# USBHeaders.net
KiCad netlist of a schematic drawn in Altium Designer
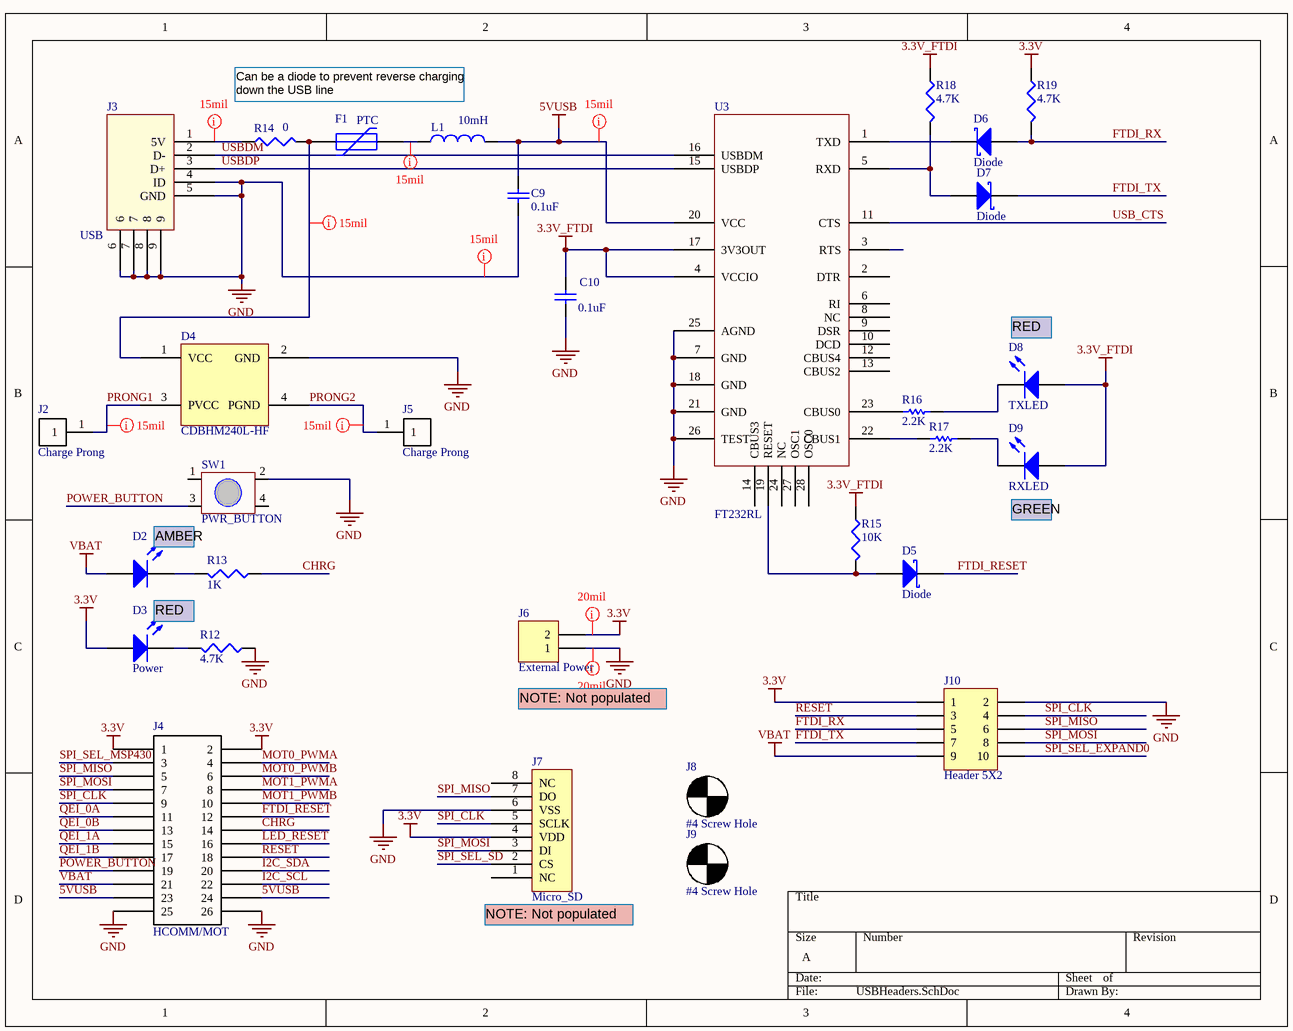
[diagram p0: USBHeaders.SchDoc]

(export (version "E")
  (design (tool "Eeschema 10.0.6"))
  (components
    (comp (ref "C9")
      (value "0.1uF")
      (footprint "CAPC1005L")
      (description "Capacitor")
      (fields (field (name "PUBLISHER") "Altium Limited"))
      (libsource (lib "Miscellaneous Devices") (part "Cap"))
    )
    (comp (ref "C10")
      (value "0.1uF")
      (footprint "CAPC1005L")
      (description "Capacitor")
      (fields (field (name "PUBLISHER") "Altium Limited"))
      (libsource (lib "Miscellaneous Devices") (part "Cap"))
    )
    (comp (ref "D2")
      (value "Charge")
      (footprint "SurfaceMount(603)")
      (description "Typical RED, GREEN, YELLOW, AMBER GaAs LED")
      (fields (field (name "PUBLISHER") "Altium Limited"))
      (libsource (lib "") (part "LED2_1"))
    )
    (comp (ref "D3") (value "Power") (footprint "SurfaceMount(603)") (libsource (lib "mrone") (part "LED")))
    (comp (ref "D4")
      (value "CDBHM240L-HF")
      (footprint "DIODEARRAY_2AMPS")
      (fields (field (name "MPN") "CDBHM240L-HF"))
      (libsource (lib "mrone") (part "DiodeArray2Amps"))
    )
    (comp (ref "D5")
      (value "Diode")
      (footprint "SurfaceMount(603)")
      (libsource (lib "mrone") (part "SchottkeyDiode"))
    )
    (comp (ref "D6")
      (value "Diode")
      (footprint "SurfaceMount(603)")
      (libsource (lib "mrone") (part "SchottkeyDiode"))
    )
    (comp (ref "D7")
      (value "Diode")
      (footprint "SurfaceMount(603)")
      (libsource (lib "mrone") (part "SchottkeyDiode"))
    )
    (comp (ref "D8")
      (value "TXLED")
      (footprint "SurfaceMount(603)")
      (description "Typical RED, GREEN, YELLOW, AMBER GaAs LED")
      (fields (field (name "PUBLISHER") "Altium Limited"))
      (libsource (lib "Miscellaneous Devices") (part "LED2"))
    )
    (comp (ref "D9")
      (value "RXLED")
      (footprint "SurfaceMount(603)")
      (description "Typical RED, GREEN, YELLOW, AMBER GaAs LED")
      (fields (field (name "PUBLISHER") "Altium Limited"))
      (libsource (lib "Miscellaneous Devices") (part "LED2"))
    )
    (comp (ref "F1")
      (value "PTC")
      (footprint "ERJ8G-1206")
      (description "Fuse")
      (fields (field (name "PUBLISHER") "Altium Limited"))
      (libsource (lib "mrone") (part "PTC_FUSE"))
    )
    (comp (ref "J2")
      (value "Charge Prong")
      (footprint "CHARGING_PRONG")
      (description "Charging Prong Hole with Plating")
      (libsource (lib "mrone") (part "CHARGE_PRONG"))
    )
    (comp (ref "J3")
      (value "USB")
      (footprint "USB Minib (thru-hole)")
      (libsource (lib "mrone") (part "USB-ConnTH"))
    )
    (comp (ref "J4")
      (value "HCOMM/MOT")
      (footprint "HeaderSM 13x2")
      (description "Header, 2X20, 50mil, IDC")
      (libsource (lib "mrone") (part "HCOMM/HMOT"))
    )
    (comp (ref "J5")
      (value "Charge Prong")
      (footprint "CHARGING_PRONG")
      (description "Charging Prong Hole with Plating")
      (libsource (lib "mrone") (part "CHARGE_PRONG"))
    )
    (comp (ref "J6")
      (value "External Power")
      (footprint "HDR1X2")
      (description "Header, 2-Pin")
      (fields (field (name "PUBLISHER") "Altium Limited"))
      (libsource (lib "Miscellaneous Connectors") (part "Header 2"))
    )
    (comp (ref "J7") (value "Micro_SD") (footprint "MICRO_SD") (libsource (lib "mrone") (part "MICRO_SD")))
    (comp (ref "J8")
      (value "#4 Screw Hole")
      (footprint "#4_Screw_Hole")
      (description "A mechanical hole for mounting the board")
      (libsource (lib "mrone") (part "Mechanical_Hole"))
    )
    (comp (ref "J9")
      (value "#4 Screw Hole")
      (footprint "#4_Screw_Hole")
      (description "A mechanical hole for mounting the board")
      (libsource (lib "mrone") (part "Mechanical_Hole"))
    )
    (comp (ref "J10")
      (value "Header 5X2")
      (footprint "HDR2X5")
      (description "Header, 5-Pin, Dual row")
      (fields (field (name "PUBLISHER") "Altium Limited"))
      (libsource (lib "mrone") (part "Header 5X2"))
    )
    (comp (ref "L1")
      (value "10mH")
      (footprint "INDC2012L")
      (description "Inductor")
      (fields (field (name "PUBLISHER") "Altium Limited"))
      (libsource (lib "Miscellaneous Devices") (part "Inductor"))
    )
    (comp (ref "R12")
      (value "4.7K")
      (footprint "RESC1608L")
      (description "Resistor")
      (fields (field (name "Comment") "Res3") (field (name "PUBLISHER") "Altium Limited"))
      (libsource (lib "Miscellaneous Devices") (part "Res3"))
    )
    (comp (ref "R13")
      (value "1K")
      (footprint "RESC1608L")
      (description "Resistor")
      (fields (field (name "Comment") "Res3") (field (name "PUBLISHER") "Altium Limited"))
      (libsource (lib "Miscellaneous Devices") (part "Res3"))
    )
    (comp (ref "R14")
      (value "0")
      (footprint "RESC1608L")
      (description "Resistor")
      (fields (field (name "Comment") "Res3") (field (name "PUBLISHER") "Altium Limited"))
      (libsource (lib "Miscellaneous Devices") (part "Res3"))
    )
    (comp (ref "R15")
      (value "10K")
      (footprint "RESC1608L")
      (description "Resistor")
      (fields (field (name "Comment") "Res3") (field (name "PUBLISHER") "Altium Limited"))
      (libsource (lib "Miscellaneous Devices") (part "Res3"))
    )
    (comp (ref "R16")
      (value "2.2K")
      (footprint "RESC1608L")
      (description "Resistor")
      (fields (field (name "PUBLISHER") "Altium Limited"))
      (libsource (lib "Miscellaneous Devices") (part "Res1"))
    )
    (comp (ref "R17")
      (value "2.2K")
      (footprint "RESC1608L")
      (description "Resistor")
      (fields (field (name "PUBLISHER") "Altium Limited"))
      (libsource (lib "Miscellaneous Devices") (part "Res1"))
    )
    (comp (ref "R18")
      (value "4.7K")
      (footprint "RESC1608L")
      (description "Resistor")
      (fields (field (name "Comment") "Res3") (field (name "PUBLISHER") "Altium Limited"))
      (libsource (lib "Miscellaneous Devices") (part "Res3"))
    )
    (comp (ref "R19")
      (value "4.7K")
      (footprint "RESC1608L")
      (description "Resistor")
      (fields (field (name "Comment") "Res3") (field (name "PUBLISHER") "Altium Limited"))
      (libsource (lib "Miscellaneous Devices") (part "Res3"))
    )
    (comp (ref "SW1")
      (value "PWR_BUTTON")
      (footprint "SwitchTall-TL330")
      (libsource (lib "mrone") (part "Switch-TL330"))
    )
    (comp (ref "U3") (value "FT232RL") (footprint "SSOP-28") (libsource (lib "mrone") (part "FT232RL")))
  )
  (nets
    (net (code "2") (name "/CHRG") (class "Default")
      (node (ref "J4") (pin "14") (pinfunction "14_14") (pintype "passive"))
      (node (ref "R13") (pin "1") (pinfunction "1_1") (pintype "passive"))
    )
    (net (code "3") (name "/FTDI_RESET") (class "Default")
      (node (ref "D5") (pin "1") (pinfunction "K_1") (pintype "passive"))
      (node (ref "J4") (pin "12") (pinfunction "12_12") (pintype "passive"))
    )
    (net (code "4") (name "/FTDI_RX") (class "Default")
      (node (ref "D6") (pin "2") (pinfunction "A_2") (pintype "passive"))
      (node (ref "J10") (pin "5") (pinfunction "5_5") (pintype "passive"))
      (node (ref "R19") (pin "2") (pinfunction "2_2") (pintype "passive"))
    )
    (net (code "5") (name "/FTDI_TX") (class "Default")
      (node (ref "D7") (pin "1") (pinfunction "K_1") (pintype "passive"))
      (node (ref "J10") (pin "7") (pinfunction "7_7") (pintype "passive"))
    )
    (net (code "6") (name "/I2C_SCL") (class "Default")
      (node (ref "J4") (pin "22") (pinfunction "22_22") (pintype "passive"))
    )
    (net (code "7") (name "/I2C_SDA") (class "Default")
      (node (ref "J4") (pin "20") (pinfunction "20_20") (pintype "passive"))
    )
    (net (code "8") (name "/LED_RESET") (class "Default")
      (node (ref "J4") (pin "16") (pinfunction "16_16") (pintype "passive"))
    )
    (net (code "9") (name "/MOT0_PWMA") (class "Default")
      (node (ref "J4") (pin "4") (pinfunction "4_4") (pintype "passive"))
    )
    (net (code "10") (name "/MOT0_PWMB") (class "Default")
      (node (ref "J4") (pin "6") (pinfunction "6_6") (pintype "passive"))
    )
    (net (code "11") (name "/MOT1_PWMA") (class "Default")
      (node (ref "J4") (pin "8") (pinfunction "8_8") (pintype "passive"))
    )
    (net (code "12") (name "/MOT1_PWMB") (class "Default")
      (node (ref "J4") (pin "10") (pinfunction "10_10") (pintype "passive"))
    )
    (net (code "13") (name "/POWER_BUTTON") (class "Default")
      (node (ref "J4") (pin "19") (pinfunction "19_19") (pintype "passive"))
      (node (ref "SW1") (pin "3") (pinfunction "3_3") (pintype "passive"))
    )
    (net (code "14") (name "/PRONG1") (class "Default")
      (node (ref "D4") (pin "3") (pinfunction "PVCC_3") (pintype "passive"))
      (node (ref "J2") (pin "1") (pinfunction "1_1") (pintype "passive"))
    )
    (net (code "15") (name "/PRONG2") (class "Default")
      (node (ref "D4") (pin "4") (pinfunction "PGND_4") (pintype "passive"))
      (node (ref "J5") (pin "1") (pinfunction "1_1") (pintype "passive"))
    )
    (net (code "16") (name "/QEI_0A") (class "Default")
      (node (ref "J4") (pin "11") (pinfunction "11_11") (pintype "passive"))
    )
    (net (code "17") (name "/QEI_0B") (class "Default")
      (node (ref "J4") (pin "13") (pinfunction "13_13") (pintype "passive"))
    )
    (net (code "18") (name "/QEI_1A") (class "Default")
      (node (ref "J4") (pin "15") (pinfunction "15_15") (pintype "passive"))
    )
    (net (code "19") (name "/QEI_1B") (class "Default")
      (node (ref "J4") (pin "17") (pinfunction "17_17") (pintype "passive"))
    )
    (net (code "20") (name "/RESET") (class "Default")
      (node (ref "J10") (pin "3") (pinfunction "3_3") (pintype "passive"))
      (node (ref "J4") (pin "18") (pinfunction "18_18") (pintype "passive"))
    )
    (net (code "21") (name "/SPI_CLK") (class "Default")
      (node (ref "J10") (pin "4") (pinfunction "4_4") (pintype "passive"))
      (node (ref "J4") (pin "9") (pinfunction "9_9") (pintype "passive"))
      (node (ref "J7") (pin "5") (pinfunction "SCLK_5") (pintype "passive"))
    )
    (net (code "22") (name "/SPI_MISO") (class "Default")
      (node (ref "J10") (pin "6") (pinfunction "6_6") (pintype "passive"))
      (node (ref "J4") (pin "5") (pinfunction "5_5") (pintype "passive"))
      (node (ref "J7") (pin "7") (pinfunction "DO_7") (pintype "passive"))
    )
    (net (code "23") (name "/SPI_MOSI") (class "Default")
      (node (ref "J10") (pin "8") (pinfunction "8_8") (pintype "passive"))
      (node (ref "J4") (pin "7") (pinfunction "7_7") (pintype "passive"))
      (node (ref "J7") (pin "3") (pinfunction "DI_3") (pintype "passive"))
    )
    (net (code "24") (name "/SPI_SEL_EXPAND0") (class "Default")
      (node (ref "J10") (pin "10") (pinfunction "10_10") (pintype "passive"))
    )
    (net (code "25") (name "/SPI_SEL_MSP430") (class "Default")
      (node (ref "J4") (pin "3") (pinfunction "3_3") (pintype "passive"))
    )
    (net (code "26") (name "/SPI_SEL_SD") (class "Default")
      (node (ref "J7") (pin "2") (pinfunction "CS_2") (pintype "passive"))
    )
    (net (code "27") (name "/USBDM") (class "Default")
      (node (ref "J3") (pin "2") (pinfunction "D-_2") (pintype "passive"))
      (node (ref "U3") (pin "16") (pinfunction "USBDM_16") (pintype "passive"))
    )
    (net (code "28") (name "/USBDP") (class "Default")
      (node (ref "J3") (pin "3") (pinfunction "D+_3") (pintype "passive"))
      (node (ref "U3") (pin "15") (pinfunction "USBDP_15") (pintype "passive"))
    )
    (net (code "29") (name "/USB_CTS") (class "Default")
      (node (ref "U3") (pin "11") (pinfunction "CTS_11") (pintype "passive"))
    )
    (net (code "30") (name "3.3V") (class "Default")
      (node (ref "D3") (pin "1") (pinfunction "A_1") (pintype "passive"))
      (node (ref "J10") (pin "1") (pinfunction "1_1") (pintype "passive"))
      (node (ref "J4") (pin "1") (pinfunction "1_1") (pintype "passive"))
      (node (ref "J4") (pin "2") (pinfunction "2_2") (pintype "passive"))
      (node (ref "J6") (pin "2") (pinfunction "2_2") (pintype "passive"))
      (node (ref "J7") (pin "4") (pinfunction "VDD_4") (pintype "passive"))
      (node (ref "R19") (pin "1") (pinfunction "1_1") (pintype "passive"))
    )
    (net (code "31") (name "3.3V_FTDI") (class "Default")
      (node (ref "C10") (pin "2") (pinfunction "2_2") (pintype "passive"))
      (node (ref "D8") (pin "1") (pinfunction "A_1") (pintype "passive"))
      (node (ref "D9") (pin "1") (pinfunction "A_1") (pintype "passive"))
      (node (ref "R15") (pin "1") (pinfunction "1_1") (pintype "passive"))
      (node (ref "R18") (pin "1") (pinfunction "1_1") (pintype "passive"))
      (node (ref "U3") (pin "17") (pinfunction "3V3OUT_17") (pintype "passive"))
      (node (ref "U3") (pin "4") (pinfunction "VCCIO_4") (pintype "passive"))
    )
    (net (code "32") (name "5VUSB") (class "Default")
      (node (ref "C9") (pin "2") (pinfunction "2_2") (pintype "passive"))
      (node (ref "J4") (pin "23") (pinfunction "23_23") (pintype "passive"))
      (node (ref "J4") (pin "24") (pinfunction "24_24") (pintype "passive"))
      (node (ref "L1") (pin "2") (pinfunction "2_2") (pintype "passive"))
      (node (ref "U3") (pin "20") (pinfunction "VCC_20") (pintype "passive"))
    )
    (net (code "33") (name "GND") (class "Default")
      (node (ref "C10") (pin "1") (pinfunction "1_1") (pintype "passive"))
      (node (ref "C9") (pin "1") (pinfunction "1_1") (pintype "passive"))
      (node (ref "D4") (pin "2") (pinfunction "GND_2") (pintype "passive"))
      (node (ref "J10") (pin "2") (pinfunction "2_2") (pintype "passive"))
      (node (ref "J3") (pin "4") (pinfunction "ID_4") (pintype "passive"))
      (node (ref "J3") (pin "5") (pinfunction "GND_5") (pintype "passive"))
      (node (ref "J3") (pin "6") (pinfunction "6_6") (pintype "passive"))
      (node (ref "J3") (pin "7") (pinfunction "7_7") (pintype "passive"))
      (node (ref "J3") (pin "8") (pinfunction "8_8") (pintype "passive"))
      (node (ref "J3") (pin "9") (pinfunction "9_9") (pintype "passive"))
      (node (ref "J4") (pin "25") (pinfunction "25_25") (pintype "passive"))
      (node (ref "J4") (pin "26") (pinfunction "26_26") (pintype "passive"))
      (node (ref "J6") (pin "1") (pinfunction "1_1") (pintype "passive"))
      (node (ref "J7") (pin "6") (pinfunction "VSS_6") (pintype "passive"))
      (node (ref "R12") (pin "1") (pinfunction "1_1") (pintype "passive"))
      (node (ref "SW1") (pin "2") (pinfunction "2_2") (pintype "passive"))
      (node (ref "U3") (pin "18") (pinfunction "GND_18") (pintype "passive"))
      (node (ref "U3") (pin "21") (pinfunction "GND_21") (pintype "passive"))
      (node (ref "U3") (pin "25") (pinfunction "AGND_25") (pintype "passive"))
      (node (ref "U3") (pin "26") (pinfunction "TEST_26") (pintype "passive"))
      (node (ref "U3") (pin "7") (pinfunction "GND_7") (pintype "passive"))
    )
    (net (code "34") (name "Net-(D2-K)") (class "Default")
      (node (ref "D2") (pin "2") (pinfunction "K_2") (pintype "passive"))
      (node (ref "R13") (pin "2") (pinfunction "2_2") (pintype "passive"))
    )
    (net (code "35") (name "Net-(D3-K)") (class "Default")
      (node (ref "D3") (pin "2") (pinfunction "K_2") (pintype "passive"))
      (node (ref "R12") (pin "2") (pinfunction "2_2") (pintype "passive"))
    )
    (net (code "36") (name "Net-(D4-VCC)") (class "Default")
      (node (ref "D4") (pin "1") (pinfunction "VCC_1") (pintype "passive"))
      (node (ref "F1") (pin "2") (pinfunction "2_2") (pintype "passive"))
      (node (ref "R14") (pin "2") (pinfunction "2_2") (pintype "passive"))
    )
    (net (code "37") (name "Net-(D5-A)") (class "Default")
      (node (ref "D5") (pin "2") (pinfunction "A_2") (pintype "passive"))
      (node (ref "R15") (pin "2") (pinfunction "2_2") (pintype "passive"))
      (node (ref "U3") (pin "19") (pinfunction "RESET_19") (pintype "passive"))
    )
    (net (code "38") (name "Net-(D6-K)") (class "Default")
      (node (ref "D6") (pin "1") (pinfunction "K_1") (pintype "passive"))
      (node (ref "U3") (pin "1") (pinfunction "TXD_1") (pintype "passive"))
    )
    (net (code "39") (name "Net-(D7-A)") (class "Default")
      (node (ref "D7") (pin "2") (pinfunction "A_2") (pintype "passive"))
      (node (ref "R18") (pin "2") (pinfunction "2_2") (pintype "passive"))
      (node (ref "U3") (pin "5") (pinfunction "RXD_5") (pintype "passive"))
    )
    (net (code "40") (name "Net-(D8-K)") (class "Default")
      (node (ref "D8") (pin "2") (pinfunction "K_2") (pintype "passive"))
      (node (ref "R16") (pin "2") (pinfunction "2_2") (pintype "passive"))
    )
    (net (code "41") (name "Net-(D9-K)") (class "Default")
      (node (ref "D9") (pin "2") (pinfunction "K_2") (pintype "passive"))
      (node (ref "R17") (pin "2") (pinfunction "2_2") (pintype "passive"))
    )
    (net (code "42") (name "Net-(F1-Pad1)") (class "Default")
      (node (ref "F1") (pin "1") (pinfunction "1_1") (pintype "passive"))
      (node (ref "L1") (pin "1") (pinfunction "1_1") (pintype "passive"))
    )
    (net (code "43") (name "Net-(J3-5V)") (class "Default")
      (node (ref "J3") (pin "1") (pinfunction "5V_1") (pintype "passive"))
      (node (ref "R14") (pin "1") (pinfunction "1_1") (pintype "passive"))
    )
    (net (code "44") (name "Net-(U3-CBUS0)") (class "Default")
      (node (ref "R16") (pin "1") (pinfunction "1_1") (pintype "passive"))
      (node (ref "U3") (pin "23") (pinfunction "CBUS0_23") (pintype "passive"))
    )
    (net (code "45") (name "Net-(U3-CBUS1)") (class "Default")
      (node (ref "R17") (pin "1") (pinfunction "1_1") (pintype "passive"))
      (node (ref "U3") (pin "22") (pinfunction "CBUS1_22") (pintype "passive"))
    )
    (net (code "46") (name "VBAT") (class "Default")
      (node (ref "D2") (pin "1") (pinfunction "A_1") (pintype "passive"))
      (node (ref "J10") (pin "9") (pinfunction "9_9") (pintype "passive"))
      (node (ref "J4") (pin "21") (pinfunction "21_21") (pintype "passive"))
    )
    (net (code "47") (name "unconnected-(J7-NC-Pad1)") (class "Default")
      (node (ref "J7") (pin "1") (pinfunction "NC_1") (pintype "passive"))
    )
    (net (code "48") (name "unconnected-(J7-NC-Pad8)") (class "Default")
      (node (ref "J7") (pin "8") (pinfunction "NC_8") (pintype "passive"))
    )
    (net (code "49") (name "unconnected-(SW1-Pad1)") (class "Default")
      (node (ref "SW1") (pin "1") (pinfunction "1_1") (pintype "passive"))
    )
    (net (code "50") (name "unconnected-(SW1-Pad4)") (class "Default")
      (node (ref "SW1") (pin "4") (pinfunction "4_4") (pintype "passive"))
    )
    (net (code "51") (name "unconnected-(U3-CBUS2-Pad13)") (class "Default")
      (node (ref "U3") (pin "13") (pinfunction "CBUS2_13") (pintype "passive"))
    )
    (net (code "52") (name "unconnected-(U3-CBUS3-Pad14)") (class "Default")
      (node (ref "U3") (pin "14") (pinfunction "CBUS3_14") (pintype "passive"))
    )
    (net (code "53") (name "unconnected-(U3-CBUS4-Pad12)") (class "Default")
      (node (ref "U3") (pin "12") (pinfunction "CBUS4_12") (pintype "passive"))
    )
    (net (code "54") (name "unconnected-(U3-DCD-Pad10)") (class "Default")
      (node (ref "U3") (pin "10") (pinfunction "DCD_10") (pintype "passive"))
    )
    (net (code "55") (name "unconnected-(U3-DSR-Pad9)") (class "Default")
      (node (ref "U3") (pin "9") (pinfunction "DSR_9") (pintype "passive"))
    )
    (net (code "56") (name "unconnected-(U3-DTR-Pad2)") (class "Default")
      (node (ref "U3") (pin "2") (pinfunction "DTR_2") (pintype "passive"))
    )
    (net (code "57") (name "unconnected-(U3-NC-Pad8)") (class "Default")
      (node (ref "U3") (pin "8") (pinfunction "NC_8") (pintype "passive"))
    )
    (net (code "58") (name "unconnected-(U3-NC-Pad24)") (class "Default")
      (node (ref "U3") (pin "24") (pinfunction "NC_24") (pintype "passive"))
    )
    (net (code "59") (name "unconnected-(U3-OSC0-Pad28)") (class "Default")
      (node (ref "U3") (pin "28") (pinfunction "OSC0_28") (pintype "passive"))
    )
    (net (code "60") (name "unconnected-(U3-OSC1-Pad27)") (class "Default")
      (node (ref "U3") (pin "27") (pinfunction "OSC1_27") (pintype "passive"))
    )
    (net (code "61") (name "unconnected-(U3-RI-Pad6)") (class "Default")
      (node (ref "U3") (pin "6") (pinfunction "RI_6") (pintype "passive"))
    )
    (net (code "62") (name "unconnected-(U3-RTS-Pad3)") (class "Default")
      (node (ref "U3") (pin "3") (pinfunction "RTS_3") (pintype "passive"))
    )
  )
)
